# IR.net
KiCad netlist of a schematic drawn in Altium Designer
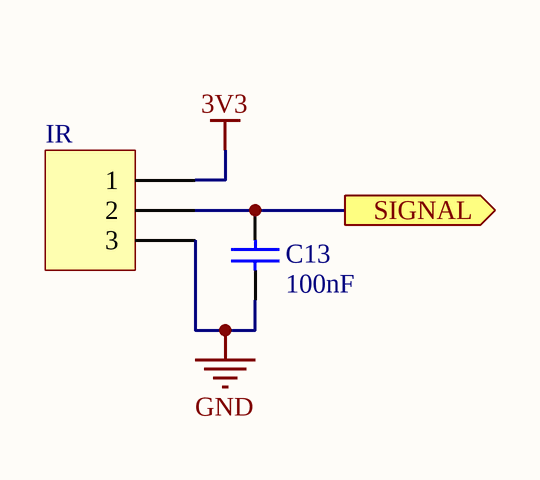
[diagram p0: IR.SchDoc]

(export (version "E")
  (design (tool "Eeschema 10.0.6"))
  (components
    (comp (ref "C13")
      (value "100nF")
      (footprint "J1-0603")
      (description "Capacitor")
      (fields (field (name "Comment") "Cap") (field (name "PUBLISHER") "Altium Limited"))
      (libsource (lib "Miscellaneous Devices") (part "Cap"))
    )
    (comp (ref "IR")
      (value "Header 3")
      (footprint "HDR1X3")
      (description "Header, 3-Pin")
      (fields (field (name "PUBLISHER") "Altium Limited"))
      (libsource (lib "Miscellaneous Connectors") (part "Header 3"))
    )
  )
  (nets
    (net (code "1") (name "/SIGNAL") (class "Default")
      (node (ref "C13") (pin "2") (pinfunction "2_2") (pintype "passive"))
      (node (ref "IR") (pin "2") (pinfunction "2_2") (pintype "passive"))
    )
    (net (code "2") (name "3V3") (class "Default")
      (node (ref "IR") (pin "1") (pinfunction "1_1") (pintype "passive"))
    )
    (net (code "3") (name "GND") (class "Default")
      (node (ref "C13") (pin "1") (pinfunction "1_1") (pintype "passive"))
      (node (ref "IR") (pin "3") (pinfunction "3_3") (pintype "passive"))
    )
  )
)
